# QUDONG.net
KiCad netlist of a schematic drawn in Altium Designer
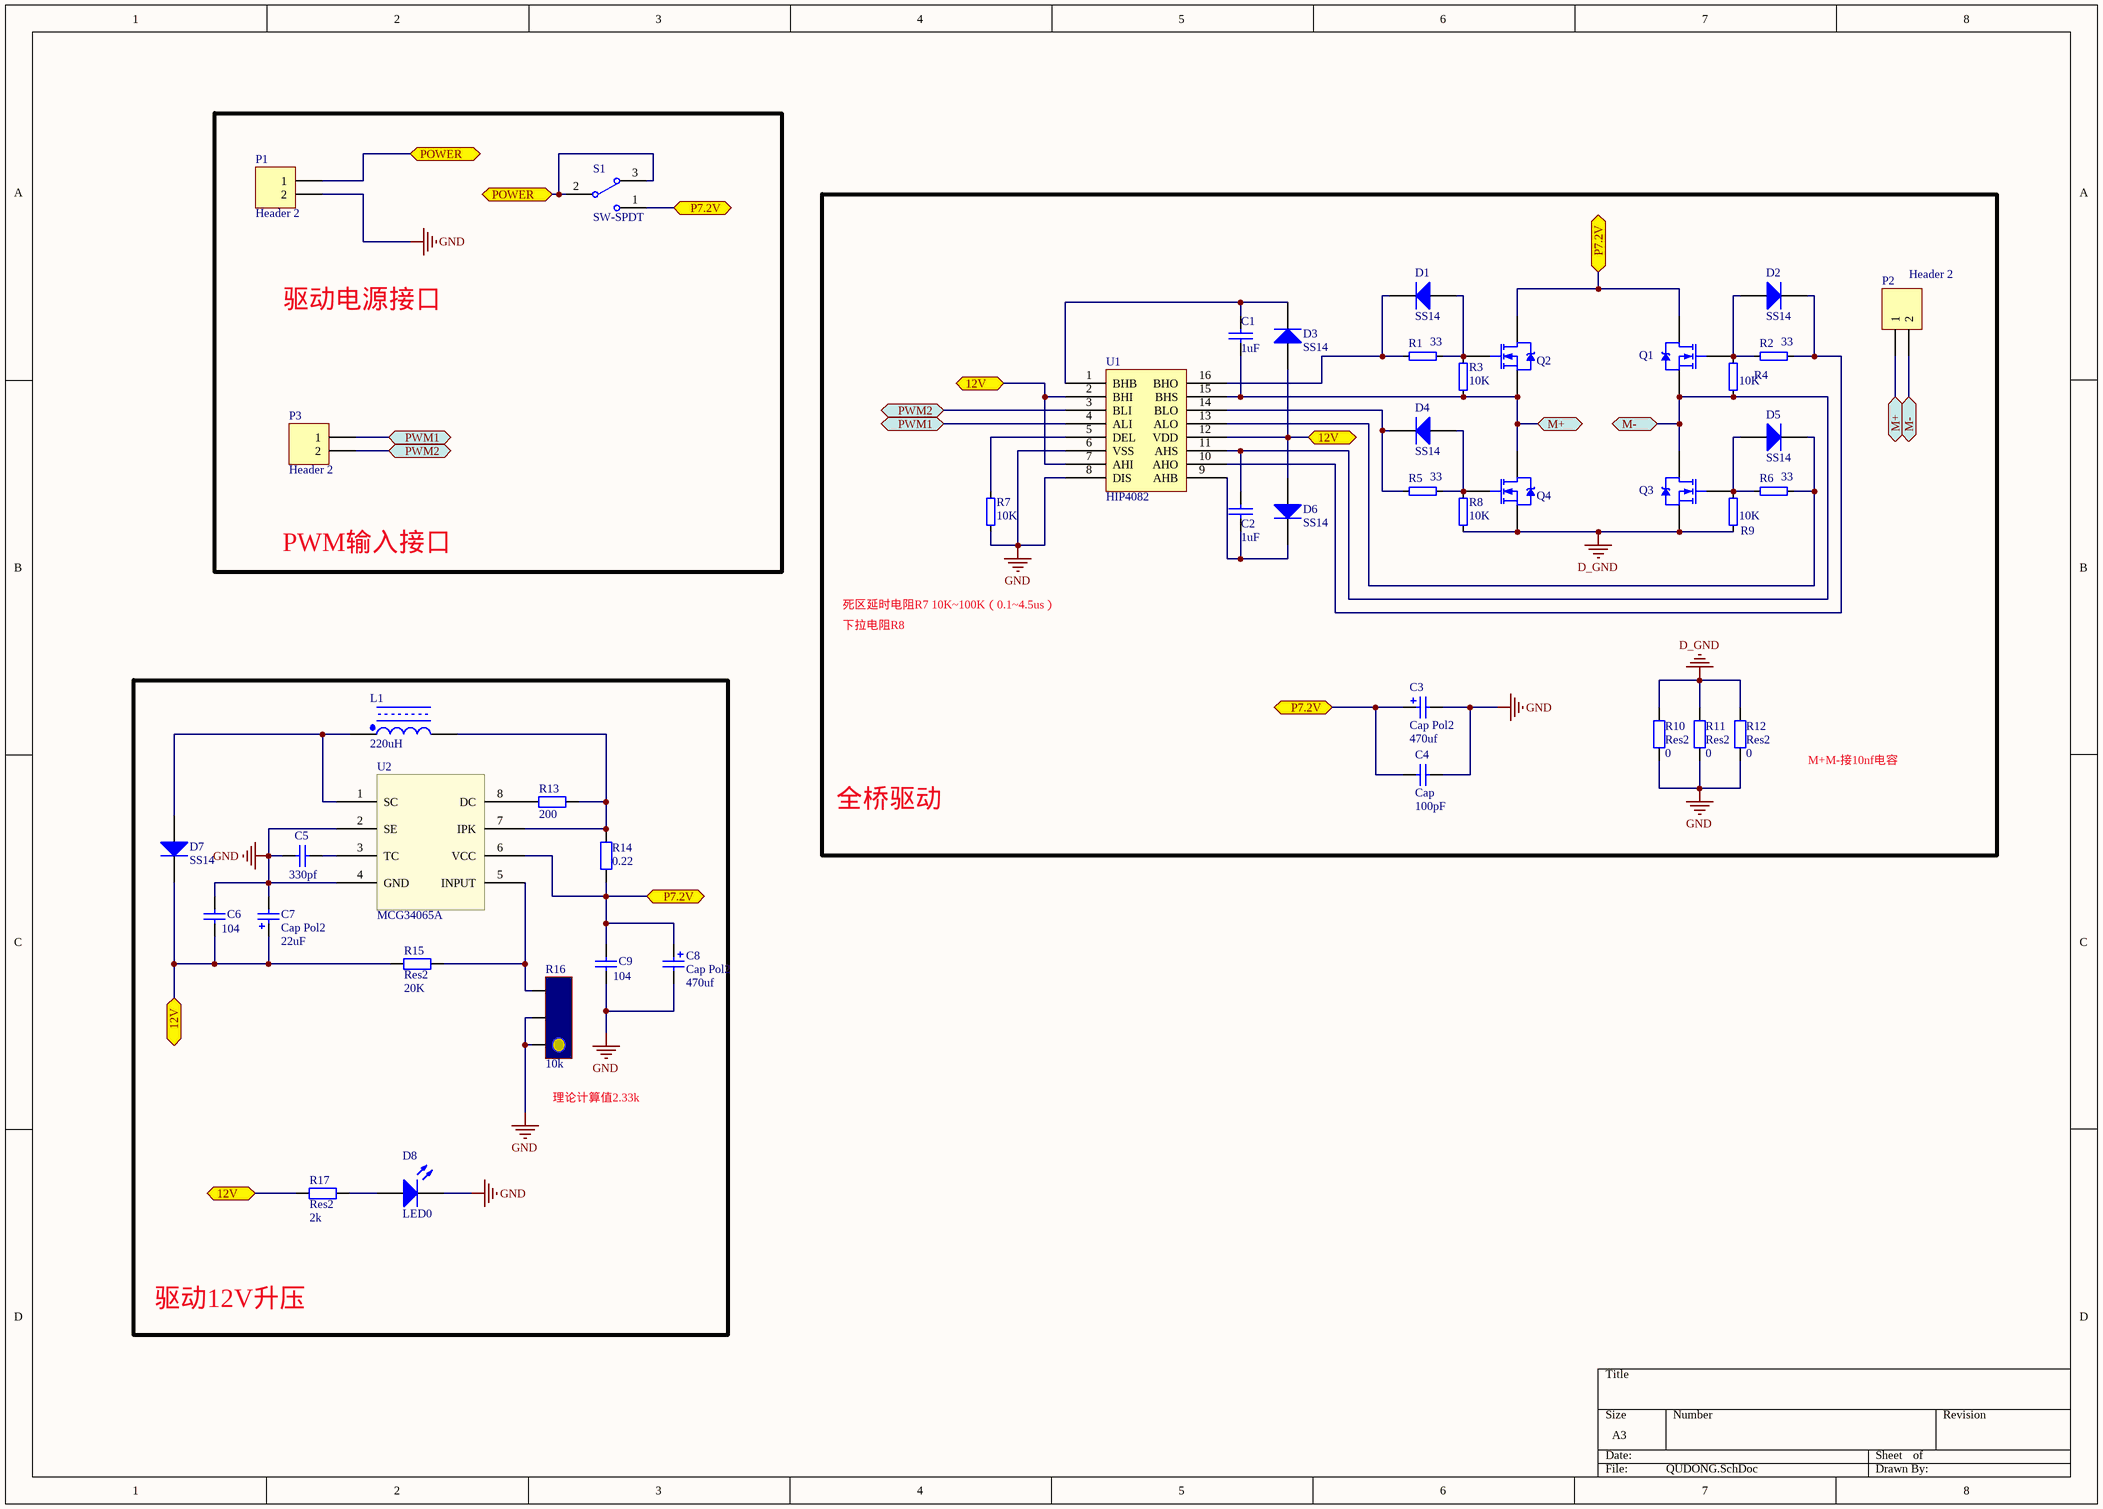
[diagram p0: QUDONG.SchDoc]

(export (version "E")
  (design (tool "Eeschema 10.0.6"))
  (components
    (comp (ref "C1")
      (value "1uF")
      (footprint "C-0805")
      (description "Capacitor")
      (libsource (lib "ZQ元件库") (part "CAP"))
    )
    (comp (ref "C2")
      (value "1uF")
      (footprint "C-0805")
      (description "Capacitor")
      (libsource (lib "ZQ元件库") (part "CAP"))
    )
    (comp (ref "C3")
      (value "Cap Pol2")
      (footprint "CAP-E1")
      (description "Polarized Capacitor (Axial)")
      (fields (field (name "ALTIUM_VALUE") "470uf") (field (name "PUBLISHER") "Altium Limited"))
      (libsource (lib "Miscellaneous Devices") (part "Cap Pol2"))
    )
    (comp (ref "C4")
      (value "Cap")
      (footprint "C-0805")
      (description "Capacitor")
      (fields (field (name "ALTIUM_VALUE") "100pF") (field (name "PUBLISHER") "Altium Limited"))
      (libsource (lib "Miscellaneous Devices") (part "Cap"))
    )
    (comp (ref "C5")
      (value "330pf")
      (footprint "C-0805")
      (description "Capacitor")
      (fields (field (name "Comment") "Cap") (field (name "PUBLISHER") "Altium Limited"))
      (libsource (lib "Miscellaneous Devices") (part "Cap"))
    )
    (comp (ref "C6")
      (value "104")
      (footprint "C-0805")
      (description "Capacitor")
      (fields (field (name "Comment") "Cap") (field (name "PUBLISHER") "Altium Limited"))
      (libsource (lib "Miscellaneous Devices") (part "Cap"))
    )
    (comp (ref "C7")
      (value "Cap Pol2")
      (footprint "1206")
      (description "Polarized Capacitor (Axial)")
      (fields (field (name "ALTIUM_VALUE") "22uF") (field (name "PUBLISHER") "Altium Limited"))
      (libsource (lib "Miscellaneous Devices") (part "Cap Pol2"))
    )
    (comp (ref "C8")
      (value "Cap Pol2")
      (footprint "CAP-E1")
      (description "Polarized Capacitor (Axial)")
      (fields (field (name "ALTIUM_VALUE") "470uf") (field (name "PUBLISHER") "Altium Limited"))
      (libsource (lib "Miscellaneous Devices") (part "Cap Pol2"))
    )
    (comp (ref "C9")
      (value "104")
      (footprint "C-0805")
      (description "Capacitor")
      (fields (field (name "Comment") "Cap") (field (name "PUBLISHER") "Altium Limited"))
      (libsource (lib "Miscellaneous Devices") (part "Cap"))
    )
    (comp (ref "D1")
      (value "SS14")
      (footprint "SOT-123")
      (description "High Conductance Fast Diode")
      (fields (field (name "PUBLISHER") "Altium Limited"))
      (libsource (lib "Miscellaneous Devices") (part "Diode 1N4148"))
    )
    (comp (ref "D2")
      (value "SS14")
      (footprint "SOT-123")
      (description "High Conductance Fast Diode")
      (fields (field (name "PUBLISHER") "Altium Limited"))
      (libsource (lib "Miscellaneous Devices") (part "Diode 1N4148"))
    )
    (comp (ref "D3")
      (value "SS14")
      (footprint "DO214AA")
      (description "High Conductance Fast Diode")
      (fields (field (name "PUBLISHER") "Altium Limited"))
      (libsource (lib "Miscellaneous Devices") (part "Diode 1N4148"))
    )
    (comp (ref "D4")
      (value "SS14")
      (footprint "SOT-123")
      (description "High Conductance Fast Diode")
      (fields (field (name "PUBLISHER") "Altium Limited"))
      (libsource (lib "Miscellaneous Devices") (part "Diode 1N4148"))
    )
    (comp (ref "D5")
      (value "SS14")
      (footprint "SOT-123")
      (description "High Conductance Fast Diode")
      (fields (field (name "PUBLISHER") "Altium Limited"))
      (libsource (lib "Miscellaneous Devices") (part "Diode 1N4148"))
    )
    (comp (ref "D6")
      (value "SS14")
      (footprint "DO214AA")
      (description "High Conductance Fast Diode")
      (fields (field (name "PUBLISHER") "Altium Limited"))
      (libsource (lib "Miscellaneous Devices") (part "Diode 1N4148"))
    )
    (comp (ref "D7")
      (value "SS14")
      (footprint "DO214AA")
      (description "Default Diode")
      (fields (field (name "PUBLISHER") "Altium Limited"))
      (libsource (lib "Miscellaneous Devices") (part "Diode"))
    )
    (comp (ref "D8")
      (value "LED0")
      (footprint "6-0805_N")
      (description "Typical INFRARED GaAs LED")
      (fields (field (name "PUBLISHER") "Altium Limited"))
      (libsource (lib "Miscellaneous Devices") (part "LED0"))
    )
    (comp (ref "L1")
      (value "220uH")
      (footprint "L-SMD-7")
      (description "磁芯电感")
      (libsource (lib "电阻-电容-电感") (part "L-D-SMD"))
    )
    (comp (ref "P1")
      (value "Header 2")
      (footprint "T型插头(公)")
      (description "Header, 2-Pin")
      (fields (field (name "PUBLISHER") "Altium Limited"))
      (libsource (lib "Miscellaneous Connectors") (part "Header 2"))
    )
    (comp (ref "P2")
      (value "Header 2")
      (footprint "接线柱")
      (description "Header, 2-Pin")
      (fields (field (name "PUBLISHER") "Altium Limited"))
      (libsource (lib "") (part "Header 2_1"))
    )
    (comp (ref "P3")
      (value "Header 2")
      (footprint "2PIN-弯")
      (description "Header, 2-Pin")
      (fields (field (name "PUBLISHER") "Altium Limited"))
      (libsource (lib "Miscellaneous Connectors") (part "Header 2"))
    )
    (comp (ref "Q1") (value "IRF3205") (footprint "TO-252AA_M") (libsource (lib "常用封装") (part "IRLR7843")))
    (comp (ref "Q2") (value "IRF3205") (footprint "TO-252AA_M") (libsource (lib "常用封装") (part "IRLR7843")))
    (comp (ref "Q3") (value "IRF3205") (footprint "TO-252AA_M") (libsource (lib "常用封装") (part "IRLR7843")))
    (comp (ref "Q4") (value "IRF3205") (footprint "TO-252AA_M") (libsource (lib "常用封装") (part "IRLR7843")))
    (comp (ref "R1") (value "33") (footprint "0805") (libsource (lib "ZQ元件库") (part "RES")))
    (comp (ref "R2") (value "33") (footprint "0805") (libsource (lib "ZQ元件库") (part "RES")))
    (comp (ref "R3") (value "10K") (footprint "0805") (libsource (lib "ZQ元件库") (part "RES")))
    (comp (ref "R4") (value "10K") (footprint "0805") (libsource (lib "ZQ元件库") (part "RES")))
    (comp (ref "R5") (value "33") (footprint "0805") (libsource (lib "ZQ元件库") (part "RES")))
    (comp (ref "R6") (value "33") (footprint "0805") (libsource (lib "ZQ元件库") (part "RES")))
    (comp (ref "R7") (value "10K") (footprint "0805") (libsource (lib "ZQ元件库") (part "RES")))
    (comp (ref "R8") (value "10K") (footprint "0805") (libsource (lib "ZQ元件库") (part "RES")))
    (comp (ref "R9") (value "10K") (footprint "0805") (libsource (lib "ZQ元件库") (part "RES")))
    (comp (ref "R10")
      (value "Res2")
      (footprint "0805")
      (description "Resistor")
      (fields (field (name "ALTIUM_VALUE") "0") (field (name "PUBLISHER") "Altium Limited"))
      (libsource (lib "") (part "Res2_1"))
    )
    (comp (ref "R11")
      (value "Res2")
      (footprint "0805")
      (description "Resistor")
      (fields (field (name "ALTIUM_VALUE") "0") (field (name "PUBLISHER") "Altium Limited"))
      (libsource (lib "") (part "Res2_1"))
    )
    (comp (ref "R12")
      (value "Res2")
      (footprint "0805")
      (description "Resistor")
      (fields (field (name "ALTIUM_VALUE") "0") (field (name "PUBLISHER") "Altium Limited"))
      (libsource (lib "") (part "Res2_1"))
    )
    (comp (ref "R13")
      (value "200")
      (footprint "0805")
      (description "Resistor")
      (fields (field (name "Comment") "Res2") (field (name "PUBLISHER") "Altium Limited"))
      (libsource (lib "Miscellaneous Devices") (part "Res2"))
    )
    (comp (ref "R14")
      (value "0.22")
      (footprint "0805")
      (description "Resistor")
      (fields (field (name "Comment") "Res2") (field (name "PUBLISHER") "Altium Limited"))
      (libsource (lib "") (part "Res2_2"))
    )
    (comp (ref "R15")
      (value "Res2")
      (footprint "0805")
      (description "Resistor")
      (fields (field (name "ALTIUM_VALUE") "20K") (field (name "PUBLISHER") "Altium Limited"))
      (libsource (lib "Miscellaneous Devices") (part "Res2"))
    )
    (comp (ref "R16")
      (value "10k")
      (footprint "T-3224w")
      (fields (field (name "Comment") "RES-ADJ"))
      (libsource (lib "常用封装") (part "RES-ADJ"))
    )
    (comp (ref "R17")
      (value "Res2")
      (footprint "0805")
      (description "Resistor")
      (fields (field (name "ALTIUM_VALUE") "2k") (field (name "PUBLISHER") "Altium Limited"))
      (libsource (lib "") (part "Res2_3"))
    )
    (comp (ref "S1")
      (value "SW-SPDT")
      (footprint "SWITCH_B")
      (description "SPDT Subminiature Toggle Switch, Right Angle Mounting, Vertical Actuation")
      (fields (field (name "PUBLISHER") "Altium Limited"))
      (libsource (lib "Miscellaneous Devices") (part "SW-SPDT"))
    )
    (comp (ref "U1") (value "HIP4082") (footprint "SO-16N") (libsource (lib "SCH_IC") (part "HIP4082")))
    (comp (ref "U2") (value "MCG34065A") (footprint "SO-8") (libsource (lib "常用封装") (part "MCG34065A")))
  )
  (nets
    (net (code "1") (name "/12V") (class "Default")
      (node (ref "C6") (pin "2") (pinfunction "2_2") (pintype "passive"))
      (node (ref "C7") (pin "1") (pinfunction "1_1") (pintype "passive"))
      (node (ref "D3") (pin "1") (pinfunction "A_1") (pintype "passive"))
      (node (ref "D6") (pin "1") (pinfunction "A_1") (pintype "passive"))
      (node (ref "D7") (pin "2") (pinfunction "K_2") (pintype "passive"))
      (node (ref "R15") (pin "2") (pinfunction "2_2") (pintype "passive"))
      (node (ref "R17") (pin "1") (pinfunction "1_1") (pintype "passive"))
      (node (ref "U1") (pin "12") (pinfunction "VDD_12") (pintype "passive"))
      (node (ref "U1") (pin "2") (pinfunction "BHI_2") (pintype "passive"))
      (node (ref "U1") (pin "7") (pinfunction "AHI_7") (pintype "passive"))
    )
    (net (code "2") (name "/M+") (class "Default")
      (node (ref "C1") (pin "1") (pinfunction "1_1") (pintype "passive"))
      (node (ref "P2") (pin "1") (pinfunction "1_1") (pintype "passive"))
      (node (ref "Q2") (pin "3") (pinfunction "S_3") (pintype "passive"))
      (node (ref "Q4") (pin "4") (pinfunction "D_4") (pintype "passive"))
      (node (ref "R3") (pin "1") (pinfunction "1_1") (pintype "passive"))
      (node (ref "U1") (pin "15") (pinfunction "BHS_15") (pintype "passive"))
    )
    (net (code "3") (name "/M-") (class "Default")
      (node (ref "C2") (pin "2") (pinfunction "2_2") (pintype "passive"))
      (node (ref "P2") (pin "2") (pinfunction "2_2") (pintype "passive"))
      (node (ref "Q1") (pin "3") (pinfunction "S_3") (pintype "passive"))
      (node (ref "Q3") (pin "4") (pinfunction "D_4") (pintype "passive"))
      (node (ref "R4") (pin "1") (pinfunction "1_1") (pintype "passive"))
      (node (ref "U1") (pin "11") (pinfunction "AHS_11") (pintype "passive"))
    )
    (net (code "4") (name "/P7.2V") (class "Default")
      (node (ref "C3") (pin "1") (pinfunction "1_1") (pintype "passive"))
      (node (ref "C4") (pin "2") (pinfunction "2_2") (pintype "passive"))
      (node (ref "C8") (pin "1") (pinfunction "1_1") (pintype "passive"))
      (node (ref "C9") (pin "1") (pinfunction "1_1") (pintype "passive"))
      (node (ref "Q1") (pin "4") (pinfunction "D_4") (pintype "passive"))
      (node (ref "Q2") (pin "4") (pinfunction "D_4") (pintype "passive"))
      (node (ref "R14") (pin "2") (pinfunction "2_2") (pintype "passive"))
      (node (ref "S1") (pin "1") (pinfunction "1_1") (pintype "passive"))
      (node (ref "U2") (pin "6") (pinfunction "VCC_6") (pintype "power_in"))
    )
    (net (code "5") (name "/POWER") (class "Default")
      (node (ref "P1") (pin "1") (pinfunction "1_1") (pintype "passive"))
      (node (ref "S1") (pin "2") (pinfunction "2_2") (pintype "passive"))
      (node (ref "S1") (pin "3") (pinfunction "3_3") (pintype "passive"))
    )
    (net (code "6") (name "/PWM1") (class "Default")
      (node (ref "P3") (pin "1") (pinfunction "1_1") (pintype "passive"))
      (node (ref "U1") (pin "4") (pinfunction "ALI_4") (pintype "passive"))
    )
    (net (code "7") (name "/PWM2") (class "Default")
      (node (ref "P3") (pin "2") (pinfunction "2_2") (pintype "passive"))
      (node (ref "U1") (pin "3") (pinfunction "BLI_3") (pintype "passive"))
    )
    (net (code "8") (name "D_GND") (class "Default")
      (node (ref "Q3") (pin "3") (pinfunction "S_3") (pintype "passive"))
      (node (ref "Q4") (pin "3") (pinfunction "S_3") (pintype "passive"))
      (node (ref "R10") (pin "2") (pinfunction "2_2") (pintype "passive"))
      (node (ref "R11") (pin "2") (pinfunction "2_2") (pintype "passive"))
      (node (ref "R12") (pin "2") (pinfunction "2_2") (pintype "passive"))
      (node (ref "R8") (pin "1") (pinfunction "1_1") (pintype "passive"))
      (node (ref "R9") (pin "1") (pinfunction "1_1") (pintype "passive"))
    )
    (net (code "9") (name "GND") (class "Default")
      (node (ref "C3") (pin "2") (pinfunction "2_2") (pintype "passive"))
      (node (ref "C4") (pin "1") (pinfunction "1_1") (pintype "passive"))
      (node (ref "C5") (pin "2") (pinfunction "2_2") (pintype "passive"))
      (node (ref "C6") (pin "1") (pinfunction "1_1") (pintype "passive"))
      (node (ref "C7") (pin "2") (pinfunction "2_2") (pintype "passive"))
      (node (ref "C8") (pin "2") (pinfunction "2_2") (pintype "passive"))
      (node (ref "C9") (pin "2") (pinfunction "2_2") (pintype "passive"))
      (node (ref "D8") (pin "2") (pinfunction "K_2") (pintype "passive"))
      (node (ref "P1") (pin "2") (pinfunction "2_2") (pintype "passive"))
      (node (ref "R10") (pin "1") (pinfunction "1_1") (pintype "passive"))
      (node (ref "R11") (pin "1") (pinfunction "1_1") (pintype "passive"))
      (node (ref "R12") (pin "1") (pinfunction "1_1") (pintype "passive"))
      (node (ref "R16") (pin "2") (pinfunction "2_2") (pintype "passive"))
      (node (ref "R16") (pin "3") (pinfunction "3_3") (pintype "passive"))
      (node (ref "R7") (pin "2") (pinfunction "2_2") (pintype "passive"))
      (node (ref "U1") (pin "6") (pinfunction "VSS_6") (pintype "passive"))
      (node (ref "U1") (pin "8") (pinfunction "DIS_8") (pintype "passive"))
      (node (ref "U2") (pin "2") (pinfunction "SE_2") (pintype "passive"))
      (node (ref "U2") (pin "4") (pinfunction "GND_4") (pintype "power_in"))
    )
    (net (code "10") (name "Net-(D1-A)") (class "Default")
      (node (ref "D1") (pin "1") (pinfunction "A_1") (pintype "passive"))
      (node (ref "Q2") (pin "1") (pinfunction "G_1") (pintype "passive"))
      (node (ref "R1") (pin "2") (pinfunction "2_2") (pintype "passive"))
      (node (ref "R3") (pin "2") (pinfunction "2_2") (pintype "passive"))
    )
    (net (code "11") (name "Net-(D1-K)") (class "Default")
      (node (ref "D1") (pin "2") (pinfunction "K_2") (pintype "passive"))
      (node (ref "R1") (pin "1") (pinfunction "1_1") (pintype "passive"))
      (node (ref "U1") (pin "16") (pinfunction "BHO_16") (pintype "passive"))
    )
    (net (code "12") (name "Net-(D2-A)") (class "Default")
      (node (ref "D2") (pin "1") (pinfunction "A_1") (pintype "passive"))
      (node (ref "Q1") (pin "1") (pinfunction "G_1") (pintype "passive"))
      (node (ref "R2") (pin "1") (pinfunction "1_1") (pintype "passive"))
      (node (ref "R4") (pin "2") (pinfunction "2_2") (pintype "passive"))
    )
    (net (code "13") (name "Net-(D2-K)") (class "Default")
      (node (ref "D2") (pin "2") (pinfunction "K_2") (pintype "passive"))
      (node (ref "R2") (pin "2") (pinfunction "2_2") (pintype "passive"))
      (node (ref "U1") (pin "10") (pinfunction "AHO_10") (pintype "passive"))
    )
    (net (code "14") (name "Net-(D3-K)") (class "Default")
      (node (ref "C1") (pin "2") (pinfunction "2_2") (pintype "passive"))
      (node (ref "D3") (pin "2") (pinfunction "K_2") (pintype "passive"))
      (node (ref "U1") (pin "1") (pinfunction "BHB_1") (pintype "passive"))
    )
    (net (code "15") (name "Net-(D4-A)") (class "Default")
      (node (ref "D4") (pin "1") (pinfunction "A_1") (pintype "passive"))
      (node (ref "Q4") (pin "1") (pinfunction "G_1") (pintype "passive"))
      (node (ref "R5") (pin "2") (pinfunction "2_2") (pintype "passive"))
      (node (ref "R8") (pin "2") (pinfunction "2_2") (pintype "passive"))
    )
    (net (code "16") (name "Net-(D4-K)") (class "Default")
      (node (ref "D4") (pin "2") (pinfunction "K_2") (pintype "passive"))
      (node (ref "R5") (pin "1") (pinfunction "1_1") (pintype "passive"))
      (node (ref "U1") (pin "14") (pinfunction "BLO_14") (pintype "passive"))
    )
    (net (code "17") (name "Net-(D5-A)") (class "Default")
      (node (ref "D5") (pin "1") (pinfunction "A_1") (pintype "passive"))
      (node (ref "Q3") (pin "1") (pinfunction "G_1") (pintype "passive"))
      (node (ref "R6") (pin "1") (pinfunction "1_1") (pintype "passive"))
      (node (ref "R9") (pin "2") (pinfunction "2_2") (pintype "passive"))
    )
    (net (code "18") (name "Net-(D5-K)") (class "Default")
      (node (ref "D5") (pin "2") (pinfunction "K_2") (pintype "passive"))
      (node (ref "R6") (pin "2") (pinfunction "2_2") (pintype "passive"))
      (node (ref "U1") (pin "13") (pinfunction "ALO_13") (pintype "passive"))
    )
    (net (code "19") (name "Net-(D6-K)") (class "Default")
      (node (ref "C2") (pin "1") (pinfunction "1_1") (pintype "passive"))
      (node (ref "D6") (pin "2") (pinfunction "K_2") (pintype "passive"))
      (node (ref "U1") (pin "9") (pinfunction "AHB_9") (pintype "passive"))
    )
    (net (code "20") (name "Net-(D7-A)") (class "Default")
      (node (ref "D7") (pin "1") (pinfunction "A_1") (pintype "passive"))
      (node (ref "L1") (pin "1") (pinfunction "1_1") (pintype "passive"))
      (node (ref "U2") (pin "1") (pinfunction "SC_1") (pintype "passive"))
    )
    (net (code "21") (name "Net-(D8-A)") (class "Default")
      (node (ref "D8") (pin "1") (pinfunction "A_1") (pintype "passive"))
      (node (ref "R17") (pin "2") (pinfunction "2_2") (pintype "passive"))
    )
    (net (code "22") (name "Net-(U1-DEL)") (class "Default")
      (node (ref "R7") (pin "1") (pinfunction "1_1") (pintype "passive"))
      (node (ref "U1") (pin "5") (pinfunction "DEL_5") (pintype "passive"))
    )
    (net (code "23") (name "Net-(U2-DC)") (class "Default")
      (node (ref "R13") (pin "2") (pinfunction "2_2") (pintype "passive"))
      (node (ref "U2") (pin "8") (pinfunction "DC_8") (pintype "passive"))
    )
    (net (code "24") (name "Net-(U2-INPUT)") (class "Default")
      (node (ref "R15") (pin "1") (pinfunction "1_1") (pintype "passive"))
      (node (ref "R16") (pin "1") (pinfunction "1_1") (pintype "passive"))
      (node (ref "U2") (pin "5") (pinfunction "INPUT_5") (pintype "passive"))
    )
    (net (code "25") (name "Net-(U2-IPK)") (class "Default")
      (node (ref "L1") (pin "2") (pinfunction "2_2") (pintype "passive"))
      (node (ref "R13") (pin "1") (pinfunction "1_1") (pintype "passive"))
      (node (ref "R14") (pin "1") (pinfunction "1_1") (pintype "passive"))
      (node (ref "U2") (pin "7") (pinfunction "IPK_7") (pintype "passive"))
    )
    (net (code "26") (name "Net-(U2-TC)") (class "Default")
      (node (ref "C5") (pin "1") (pinfunction "1_1") (pintype "passive"))
      (node (ref "U2") (pin "3") (pinfunction "TC_3") (pintype "passive"))
    )
  )
)
